# MPR121.net
KiCad netlist of a schematic drawn in Altium Designer
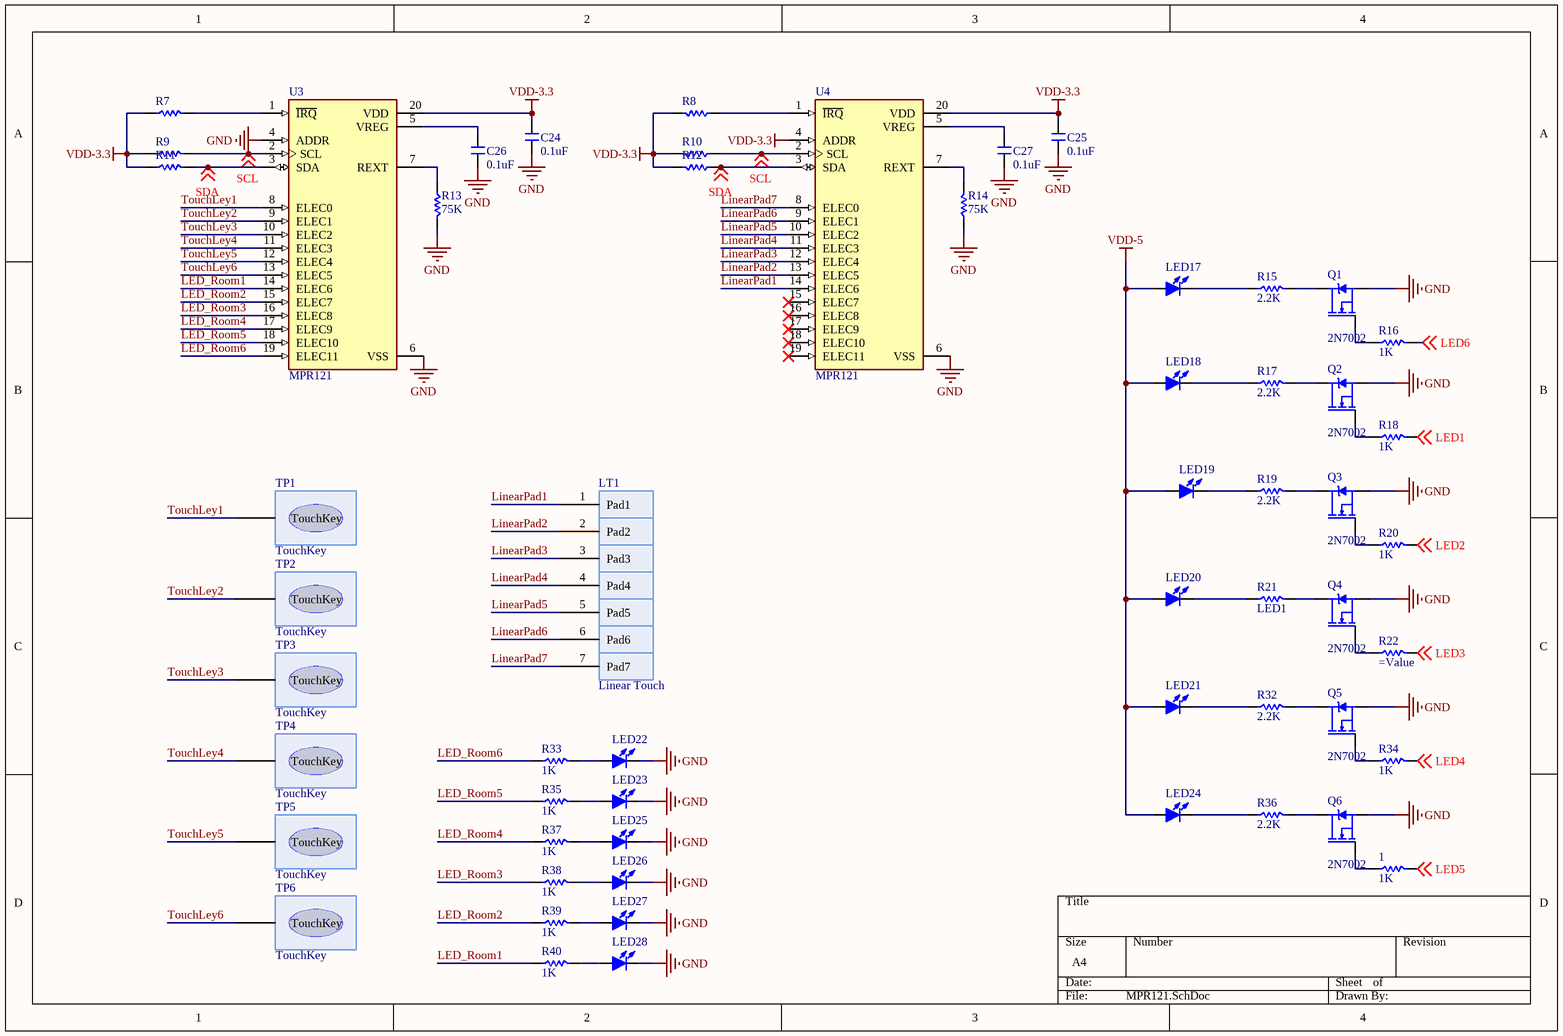
[diagram p0: MPR121.SchDoc]

(export (version "E")
  (design (tool "Eeschema 10.0.6"))
  (components
    (comp (ref "1")
      (value "1K")
      (footprint "R 0805")
      (description "Chip resistor")
      (fields (field (name "版权归属") "源创客"))
      (libsource (lib "Passive (Resistor-Capacitor-Inductor-Veristor-Ferrite)") (part "R"))
    )
    (comp (ref "C24")
      (value "0.1uF")
      (footprint "C 0603")
      (description "Non-polar patch capacitor")
      (fields (field (name "版权归属") "源创客"))
      (libsource (lib "Passive (Resistor-Capacitor-Inductor-Veristor-Ferrite)") (part "C"))
    )
    (comp (ref "C25")
      (value "0.1uF")
      (footprint "C 0603")
      (description "Non-polar patch capacitor")
      (fields (field (name "版权归属") "源创客"))
      (libsource (lib "Passive (Resistor-Capacitor-Inductor-Veristor-Ferrite)") (part "C"))
    )
    (comp (ref "C26")
      (value "0.1uF")
      (footprint "C 0603")
      (description "Non-polar patch capacitor")
      (fields (field (name "版权归属") "源创客"))
      (libsource (lib "Passive (Resistor-Capacitor-Inductor-Veristor-Ferrite)") (part "C"))
    )
    (comp (ref "C27")
      (value "0.1uF")
      (footprint "C 0603")
      (description "Non-polar patch capacitor")
      (fields (field (name "版权归属") "源创客"))
      (libsource (lib "Passive (Resistor-Capacitor-Inductor-Veristor-Ferrite)") (part "C"))
    )
    (comp (ref "LED17")
      (value "~")
      (footprint "LED 3MM-B")
      (description "Plug-in LED")
      (fields (field (name "版权归属") "源创客"))
      (libsource (lib "LED") (part "LED-3MM"))
    )
    (comp (ref "LED18")
      (value "~")
      (footprint "LED 3MM-B")
      (description "Plug-in LED")
      (fields (field (name "版权归属") "源创客"))
      (libsource (lib "LED") (part "LED-3MM"))
    )
    (comp (ref "LED19")
      (value "~")
      (footprint "LED 3MM-B")
      (description "Plug-in LED")
      (fields (field (name "版权归属") "源创客"))
      (libsource (lib "LED") (part "LED-3MM"))
    )
    (comp (ref "LED20")
      (value "~")
      (footprint "LED 3MM-B")
      (description "Plug-in LED")
      (fields (field (name "版权归属") "源创客"))
      (libsource (lib "LED") (part "LED-3MM"))
    )
    (comp (ref "LED21")
      (value "~")
      (footprint "LED 3MM-B")
      (description "Plug-in LED")
      (fields (field (name "版权归属") "源创客"))
      (libsource (lib "LED") (part "LED-3MM"))
    )
    (comp (ref "LED22")
      (value "LED-SMD")
      (footprint "LED 1206Y")
      (description "Patch LED")
      (fields (field (name "版权归属") "源创客"))
      (libsource (lib "LED") (part "LED-SMD"))
    )
    (comp (ref "LED23")
      (value "LED-SMD")
      (footprint "LED 1206Y")
      (description "Patch LED")
      (fields (field (name "版权归属") "源创客"))
      (libsource (lib "LED") (part "LED-SMD"))
    )
    (comp (ref "LED24")
      (value "~")
      (footprint "LED 3MM-B")
      (description "Plug-in LED")
      (fields (field (name "版权归属") "源创客"))
      (libsource (lib "LED") (part "LED-3MM"))
    )
    (comp (ref "LED25")
      (value "LED-SMD")
      (footprint "LED 1206Y")
      (description "Patch LED")
      (fields (field (name "版权归属") "源创客"))
      (libsource (lib "LED") (part "LED-SMD"))
    )
    (comp (ref "LED26")
      (value "LED-SMD")
      (footprint "LED 1206Y")
      (description "Patch LED")
      (fields (field (name "版权归属") "源创客"))
      (libsource (lib "LED") (part "LED-SMD"))
    )
    (comp (ref "LED27")
      (value "LED-SMD")
      (footprint "LED 1206Y")
      (description "Patch LED")
      (fields (field (name "版权归属") "源创客"))
      (libsource (lib "LED") (part "LED-SMD"))
    )
    (comp (ref "LED28")
      (value "LED-SMD")
      (footprint "LED 1206Y")
      (description "Patch LED")
      (fields (field (name "版权归属") "源创客"))
      (libsource (lib "LED") (part "LED-SMD"))
    )
    (comp (ref "LT1")
      (value "Linear Touch")
      (footprint "Linear TouchPad (7Pad)")
      (libsource (lib "Mechanical Components") (part "Linear Touch"))
    )
    (comp (ref "Q1")
      (value "2N7002")
      (footprint "SOT23-3")
      (description "N-Channel 60V 115mA (Tc) 225mW (Ta) Surface Mount SOT-23-3 (TO-236)")
      (fields (field (name "MF") "STMicroelectronics"))
      (libsource (lib "2N7002") (part "2N7002"))
    )
    (comp (ref "Q2")
      (value "2N7002")
      (footprint "SOT23-3")
      (description "N-Channel 60V 115mA (Tc) 225mW (Ta) Surface Mount SOT-23-3 (TO-236)")
      (fields (field (name "MF") "STMicroelectronics"))
      (libsource (lib "2N7002") (part "2N7002"))
    )
    (comp (ref "Q3")
      (value "2N7002")
      (footprint "SOT23-3")
      (description "N-Channel 60V 115mA (Tc) 225mW (Ta) Surface Mount SOT-23-3 (TO-236)")
      (fields (field (name "MF") "STMicroelectronics"))
      (libsource (lib "2N7002") (part "2N7002"))
    )
    (comp (ref "Q4")
      (value "2N7002")
      (footprint "SOT23-3")
      (description "N-Channel 60V 115mA (Tc) 225mW (Ta) Surface Mount SOT-23-3 (TO-236)")
      (fields (field (name "MF") "STMicroelectronics"))
      (libsource (lib "2N7002") (part "2N7002"))
    )
    (comp (ref "Q5")
      (value "2N7002")
      (footprint "SOT23-3")
      (description "N-Channel 60V 115mA (Tc) 225mW (Ta) Surface Mount SOT-23-3 (TO-236)")
      (fields (field (name "MF") "STMicroelectronics"))
      (libsource (lib "2N7002") (part "2N7002"))
    )
    (comp (ref "Q6")
      (value "2N7002")
      (footprint "SOT23-3")
      (description "N-Channel 60V 115mA (Tc) 225mW (Ta) Surface Mount SOT-23-3 (TO-236)")
      (fields (field (name "MF") "STMicroelectronics"))
      (libsource (lib "2N7002") (part "2N7002"))
    )
    (comp (ref "R7")
      (value "~")
      (footprint "R 0603")
      (description "Chip resistor")
      (fields (field (name "版权归属") "源创客"))
      (libsource (lib "Passive (Resistor-Capacitor-Inductor-Veristor-Ferrite)") (part "R"))
    )
    (comp (ref "R8")
      (value "~")
      (footprint "R 0603")
      (description "Chip resistor")
      (fields (field (name "版权归属") "源创客"))
      (libsource (lib "Passive (Resistor-Capacitor-Inductor-Veristor-Ferrite)") (part "R"))
    )
    (comp (ref "R9")
      (value "~")
      (footprint "R 0603")
      (description "Chip resistor")
      (fields (field (name "版权归属") "源创客"))
      (libsource (lib "Passive (Resistor-Capacitor-Inductor-Veristor-Ferrite)") (part "R"))
    )
    (comp (ref "R10")
      (value "~")
      (footprint "R 0603")
      (description "Chip resistor")
      (fields (field (name "版权归属") "源创客"))
      (libsource (lib "Passive (Resistor-Capacitor-Inductor-Veristor-Ferrite)") (part "R"))
    )
    (comp (ref "R11")
      (value "~")
      (footprint "R 0603")
      (description "Chip resistor")
      (fields (field (name "版权归属") "源创客"))
      (libsource (lib "Passive (Resistor-Capacitor-Inductor-Veristor-Ferrite)") (part "R"))
    )
    (comp (ref "R12")
      (value "~")
      (footprint "R 0603")
      (description "Chip resistor")
      (fields (field (name "版权归属") "源创客"))
      (libsource (lib "Passive (Resistor-Capacitor-Inductor-Veristor-Ferrite)") (part "R"))
    )
    (comp (ref "R13")
      (value "75K")
      (footprint "R 0603")
      (description "Chip resistor")
      (fields (field (name "版权归属") "源创客"))
      (libsource (lib "Passive (Resistor-Capacitor-Inductor-Veristor-Ferrite)") (part "R"))
    )
    (comp (ref "R14")
      (value "75K")
      (footprint "R 0603")
      (description "Chip resistor")
      (fields (field (name "版权归属") "源创客"))
      (libsource (lib "Passive (Resistor-Capacitor-Inductor-Veristor-Ferrite)") (part "R"))
    )
    (comp (ref "R15")
      (value "2.2K")
      (footprint "R 0805")
      (description "Chip resistor")
      (fields (field (name "版权归属") "源创客"))
      (libsource (lib "Passive (Resistor-Capacitor-Inductor-Veristor-Ferrite)") (part "R"))
    )
    (comp (ref "R16")
      (value "1K")
      (footprint "R 0805")
      (description "Chip resistor")
      (fields (field (name "版权归属") "源创客"))
      (libsource (lib "Passive (Resistor-Capacitor-Inductor-Veristor-Ferrite)") (part "R"))
    )
    (comp (ref "R17")
      (value "2.2K")
      (footprint "R 0805")
      (description "Chip resistor")
      (fields (field (name "版权归属") "源创客"))
      (libsource (lib "Passive (Resistor-Capacitor-Inductor-Veristor-Ferrite)") (part "R"))
    )
    (comp (ref "R18")
      (value "1K")
      (footprint "R 0805")
      (description "Chip resistor")
      (fields (field (name "版权归属") "源创客"))
      (libsource (lib "Passive (Resistor-Capacitor-Inductor-Veristor-Ferrite)") (part "R"))
    )
    (comp (ref "R19")
      (value "2.2K")
      (footprint "R 0805")
      (description "Chip resistor")
      (fields (field (name "版权归属") "源创客"))
      (libsource (lib "Passive (Resistor-Capacitor-Inductor-Veristor-Ferrite)") (part "R"))
    )
    (comp (ref "R20")
      (value "1K")
      (footprint "R 0805")
      (description "Chip resistor")
      (fields (field (name "版权归属") "源创客"))
      (libsource (lib "Passive (Resistor-Capacitor-Inductor-Veristor-Ferrite)") (part "R"))
    )
    (comp (ref "R21")
      (value "LED1")
      (footprint "R 0805")
      (description "Chip resistor")
      (fields (field (name "版权归属") "源创客"))
      (libsource (lib "Passive (Resistor-Capacitor-Inductor-Veristor-Ferrite)") (part "R"))
    )
    (comp (ref "R22")
      (value "~")
      (footprint "R 0805")
      (description "Chip resistor")
      (fields (field (name "版权归属") "源创客"))
      (libsource (lib "Passive (Resistor-Capacitor-Inductor-Veristor-Ferrite)") (part "R"))
    )
    (comp (ref "R32")
      (value "2.2K")
      (footprint "R 0805")
      (description "Chip resistor")
      (fields (field (name "版权归属") "源创客"))
      (libsource (lib "Passive (Resistor-Capacitor-Inductor-Veristor-Ferrite)") (part "R"))
    )
    (comp (ref "R33")
      (value "1K")
      (footprint "R 0805")
      (description "Chip resistor")
      (fields (field (name "版权归属") "源创客"))
      (libsource (lib "Passive (Resistor-Capacitor-Inductor-Veristor-Ferrite)") (part "R"))
    )
    (comp (ref "R34")
      (value "1K")
      (footprint "R 0805")
      (description "Chip resistor")
      (fields (field (name "版权归属") "源创客"))
      (libsource (lib "Passive (Resistor-Capacitor-Inductor-Veristor-Ferrite)") (part "R"))
    )
    (comp (ref "R35")
      (value "1K")
      (footprint "R 0805")
      (description "Chip resistor")
      (fields (field (name "版权归属") "源创客"))
      (libsource (lib "Passive (Resistor-Capacitor-Inductor-Veristor-Ferrite)") (part "R"))
    )
    (comp (ref "R36")
      (value "2.2K")
      (footprint "R 0805")
      (description "Chip resistor")
      (fields (field (name "版权归属") "源创客"))
      (libsource (lib "Passive (Resistor-Capacitor-Inductor-Veristor-Ferrite)") (part "R"))
    )
    (comp (ref "R37")
      (value "1K")
      (footprint "R 0805")
      (description "Chip resistor")
      (fields (field (name "版权归属") "源创客"))
      (libsource (lib "Passive (Resistor-Capacitor-Inductor-Veristor-Ferrite)") (part "R"))
    )
    (comp (ref "R38")
      (value "1K")
      (footprint "R 0805")
      (description "Chip resistor")
      (fields (field (name "版权归属") "源创客"))
      (libsource (lib "Passive (Resistor-Capacitor-Inductor-Veristor-Ferrite)") (part "R"))
    )
    (comp (ref "R39")
      (value "1K")
      (footprint "R 0805")
      (description "Chip resistor")
      (fields (field (name "版权归属") "源创客"))
      (libsource (lib "Passive (Resistor-Capacitor-Inductor-Veristor-Ferrite)") (part "R"))
    )
    (comp (ref "R40")
      (value "1K")
      (footprint "R 0805")
      (description "Chip resistor")
      (fields (field (name "版权归属") "源创客"))
      (libsource (lib "Passive (Resistor-Capacitor-Inductor-Veristor-Ferrite)") (part "R"))
    )
    (comp (ref "TP1")
      (value "TouchKey")
      (footprint "Square TouchKey (1.5cm)")
      (libsource (lib "Mechanical Components") (part "TouchKey"))
    )
    (comp (ref "TP2")
      (value "TouchKey")
      (footprint "Square TouchKey (1.5cm)")
      (libsource (lib "Mechanical Components") (part "TouchKey"))
    )
    (comp (ref "TP3")
      (value "TouchKey")
      (footprint "Square TouchKey (1.5cm)")
      (libsource (lib "Mechanical Components") (part "TouchKey"))
    )
    (comp (ref "TP4")
      (value "TouchKey")
      (footprint "Square TouchKey (1.5cm)")
      (libsource (lib "Mechanical Components") (part "TouchKey"))
    )
    (comp (ref "TP5")
      (value "TouchKey")
      (footprint "Square TouchKey (1.5cm)")
      (libsource (lib "Mechanical Components") (part "TouchKey"))
    )
    (comp (ref "TP6")
      (value "TouchKey")
      (footprint "Square TouchKey (1.5cm)")
      (libsource (lib "Mechanical Components") (part "TouchKey"))
    )
    (comp (ref "U3")
      (value "MPR121")
      (footprint "QFN-20Pin")
      (libsource (lib "Integrated Circuit") (part "MPR121"))
    )
    (comp (ref "U4")
      (value "MPR121")
      (footprint "QFN-20Pin")
      (libsource (lib "Integrated Circuit") (part "MPR121"))
    )
  )
  (nets
    (net (code "1") (name "/LED_Room1") (class "Default")
      (node (ref "R40") (pin "1") (pinfunction "1_1") (pintype "passive"))
      (node (ref "U3") (pin "14") (pinfunction "ELEC6_14") (pintype "input"))
    )
    (net (code "2") (name "/LED_Room2") (class "Default")
      (node (ref "R39") (pin "1") (pinfunction "1_1") (pintype "passive"))
      (node (ref "U3") (pin "15") (pinfunction "ELEC7_15") (pintype "input"))
    )
    (net (code "3") (name "/LED_Room3") (class "Default")
      (node (ref "R38") (pin "1") (pinfunction "1_1") (pintype "passive"))
      (node (ref "U3") (pin "16") (pinfunction "ELEC8_16") (pintype "input"))
    )
    (net (code "4") (name "/LED_Room4") (class "Default")
      (node (ref "R37") (pin "1") (pinfunction "1_1") (pintype "passive"))
      (node (ref "U3") (pin "17") (pinfunction "ELEC9_17") (pintype "input"))
    )
    (net (code "5") (name "/LED_Room5") (class "Default")
      (node (ref "R35") (pin "1") (pinfunction "1_1") (pintype "passive"))
      (node (ref "U3") (pin "18") (pinfunction "ELEC10_18") (pintype "input"))
    )
    (net (code "6") (name "/LED_Room6") (class "Default")
      (node (ref "R33") (pin "1") (pinfunction "1_1") (pintype "passive"))
      (node (ref "U3") (pin "19") (pinfunction "ELEC11_19") (pintype "input"))
    )
    (net (code "7") (name "/LinearPad1") (class "Default")
      (node (ref "LT1") (pin "1") (pinfunction "Pad1_1") (pintype "passive"))
      (node (ref "U4") (pin "14") (pinfunction "ELEC6_14") (pintype "input"))
    )
    (net (code "8") (name "/LinearPad2") (class "Default")
      (node (ref "LT1") (pin "2") (pinfunction "Pad2_2") (pintype "passive"))
      (node (ref "U4") (pin "13") (pinfunction "ELEC5_13") (pintype "input"))
    )
    (net (code "9") (name "/LinearPad3") (class "Default")
      (node (ref "LT1") (pin "3") (pinfunction "Pad3_3") (pintype "passive"))
      (node (ref "U4") (pin "12") (pinfunction "ELEC4_12") (pintype "input"))
    )
    (net (code "10") (name "/LinearPad4") (class "Default")
      (node (ref "LT1") (pin "4") (pinfunction "Pad4_4") (pintype "passive"))
      (node (ref "U4") (pin "11") (pinfunction "ELEC3_11") (pintype "input"))
    )
    (net (code "11") (name "/LinearPad5") (class "Default")
      (node (ref "LT1") (pin "5") (pinfunction "Pad5_5") (pintype "passive"))
      (node (ref "U4") (pin "10") (pinfunction "ELEC2_10") (pintype "input"))
    )
    (net (code "12") (name "/LinearPad6") (class "Default")
      (node (ref "LT1") (pin "6") (pinfunction "Pad6_6") (pintype "passive"))
      (node (ref "U4") (pin "9") (pinfunction "ELEC1_9") (pintype "input"))
    )
    (net (code "13") (name "/LinearPad7") (class "Default")
      (node (ref "LT1") (pin "7") (pinfunction "Pad7_7") (pintype "passive"))
      (node (ref "U4") (pin "8") (pinfunction "ELEC0_8") (pintype "input"))
    )
    (net (code "14") (name "/TouchLey1") (class "Default")
      (node (ref "TP1") (pin "1") (pinfunction "TouchKey_1") (pintype "passive"))
      (node (ref "U3") (pin "8") (pinfunction "ELEC0_8") (pintype "input"))
    )
    (net (code "15") (name "/TouchLey2") (class "Default")
      (node (ref "TP2") (pin "1") (pinfunction "TouchKey_1") (pintype "passive"))
      (node (ref "U3") (pin "9") (pinfunction "ELEC1_9") (pintype "input"))
    )
    (net (code "16") (name "/TouchLey3") (class "Default")
      (node (ref "TP3") (pin "1") (pinfunction "TouchKey_1") (pintype "passive"))
      (node (ref "U3") (pin "10") (pinfunction "ELEC2_10") (pintype "input"))
    )
    (net (code "17") (name "/TouchLey4") (class "Default")
      (node (ref "TP4") (pin "1") (pinfunction "TouchKey_1") (pintype "passive"))
      (node (ref "U3") (pin "11") (pinfunction "ELEC3_11") (pintype "input"))
    )
    (net (code "18") (name "/TouchLey5") (class "Default")
      (node (ref "TP5") (pin "1") (pinfunction "TouchKey_1") (pintype "passive"))
      (node (ref "U3") (pin "12") (pinfunction "ELEC4_12") (pintype "input"))
    )
    (net (code "19") (name "/TouchLey6") (class "Default")
      (node (ref "TP6") (pin "1") (pinfunction "TouchKey_1") (pintype "passive"))
      (node (ref "U3") (pin "13") (pinfunction "ELEC5_13") (pintype "input"))
    )
    (net (code "20") (name "GND") (class "Default")
      (node (ref "C24") (pin "1") (pinfunction "1_1") (pintype "passive"))
      (node (ref "C25") (pin "1") (pinfunction "1_1") (pintype "passive"))
      (node (ref "C26") (pin "1") (pinfunction "1_1") (pintype "passive"))
      (node (ref "C27") (pin "1") (pinfunction "1_1") (pintype "passive"))
      (node (ref "LED22") (pin "2") (pinfunction "K_2") (pintype "passive"))
      (node (ref "LED23") (pin "2") (pinfunction "K_2") (pintype "passive"))
      (node (ref "LED25") (pin "2") (pinfunction "K_2") (pintype "passive"))
      (node (ref "LED26") (pin "2") (pinfunction "K_2") (pintype "passive"))
      (node (ref "LED27") (pin "2") (pinfunction "K_2") (pintype "passive"))
      (node (ref "LED28") (pin "2") (pinfunction "K_2") (pintype "passive"))
      (node (ref "Q1") (pin "2") (pinfunction "S_2") (pintype "bidirectional"))
      (node (ref "Q2") (pin "2") (pinfunction "S_2") (pintype "bidirectional"))
      (node (ref "Q3") (pin "2") (pinfunction "S_2") (pintype "bidirectional"))
      (node (ref "Q4") (pin "2") (pinfunction "S_2") (pintype "bidirectional"))
      (node (ref "Q5") (pin "2") (pinfunction "S_2") (pintype "bidirectional"))
      (node (ref "Q6") (pin "2") (pinfunction "S_2") (pintype "bidirectional"))
      (node (ref "R13") (pin "2") (pinfunction "2_2") (pintype "passive"))
      (node (ref "R14") (pin "1") (pinfunction "1_1") (pintype "passive"))
      (node (ref "U3") (pin "4") (pinfunction "ADDR_4") (pintype "input"))
      (node (ref "U3") (pin "6") (pinfunction "VSS_6") (pintype "power_in"))
      (node (ref "U4") (pin "6") (pinfunction "VSS_6") (pintype "power_in"))
    )
    (net (code "21") (name "LED1") (class "Default")
      (node (ref "R18") (pin "2") (pinfunction "2_2") (pintype "passive"))
    )
    (net (code "22") (name "LED2") (class "Default")
      (node (ref "R20") (pin "2") (pinfunction "2_2") (pintype "passive"))
    )
    (net (code "23") (name "LED3") (class "Default")
      (node (ref "R22") (pin "2") (pinfunction "2_2") (pintype "passive"))
    )
    (net (code "24") (name "LED4") (class "Default")
      (node (ref "R34") (pin "2") (pinfunction "2_2") (pintype "passive"))
    )
    (net (code "25") (name "LED5") (class "Default")
      (node (ref "1") (pin "2") (pinfunction "2_2") (pintype "passive"))
    )
    (net (code "26") (name "LED6") (class "Default")
      (node (ref "R16") (pin "2") (pinfunction "2_2") (pintype "passive"))
    )
    (net (code "27") (name "Net-(LED17-K)") (class "Default")
      (node (ref "LED17") (pin "2") (pinfunction "K_2") (pintype "passive"))
      (node (ref "R15") (pin "1") (pinfunction "1_1") (pintype "passive"))
    )
    (net (code "28") (name "Net-(LED18-K)") (class "Default")
      (node (ref "LED18") (pin "2") (pinfunction "K_2") (pintype "passive"))
      (node (ref "R17") (pin "1") (pinfunction "1_1") (pintype "passive"))
    )
    (net (code "29") (name "Net-(LED19-K)") (class "Default")
      (node (ref "LED19") (pin "2") (pinfunction "K_2") (pintype "passive"))
      (node (ref "R19") (pin "1") (pinfunction "1_1") (pintype "passive"))
    )
    (net (code "30") (name "Net-(LED20-K)") (class "Default")
      (node (ref "LED20") (pin "2") (pinfunction "K_2") (pintype "passive"))
      (node (ref "R21") (pin "1") (pinfunction "1_1") (pintype "passive"))
    )
    (net (code "31") (name "Net-(LED21-K)") (class "Default")
      (node (ref "LED21") (pin "2") (pinfunction "K_2") (pintype "passive"))
      (node (ref "R32") (pin "1") (pinfunction "1_1") (pintype "passive"))
    )
    (net (code "32") (name "Net-(LED22-A)") (class "Default")
      (node (ref "LED22") (pin "1") (pinfunction "A_1") (pintype "passive"))
      (node (ref "R33") (pin "2") (pinfunction "2_2") (pintype "passive"))
    )
    (net (code "33") (name "Net-(LED23-A)") (class "Default")
      (node (ref "LED23") (pin "1") (pinfunction "A_1") (pintype "passive"))
      (node (ref "R35") (pin "2") (pinfunction "2_2") (pintype "passive"))
    )
    (net (code "34") (name "Net-(LED24-K)") (class "Default")
      (node (ref "LED24") (pin "2") (pinfunction "K_2") (pintype "passive"))
      (node (ref "R36") (pin "1") (pinfunction "1_1") (pintype "passive"))
    )
    (net (code "35") (name "Net-(LED25-A)") (class "Default")
      (node (ref "LED25") (pin "1") (pinfunction "A_1") (pintype "passive"))
      (node (ref "R37") (pin "2") (pinfunction "2_2") (pintype "passive"))
    )
    (net (code "36") (name "Net-(LED26-A)") (class "Default")
      (node (ref "LED26") (pin "1") (pinfunction "A_1") (pintype "passive"))
      (node (ref "R38") (pin "2") (pinfunction "2_2") (pintype "passive"))
    )
    (net (code "37") (name "Net-(LED27-A)") (class "Default")
      (node (ref "LED27") (pin "1") (pinfunction "A_1") (pintype "passive"))
      (node (ref "R39") (pin "2") (pinfunction "2_2") (pintype "passive"))
    )
    (net (code "38") (name "Net-(LED28-A)") (class "Default")
      (node (ref "LED28") (pin "1") (pinfunction "A_1") (pintype "passive"))
      (node (ref "R40") (pin "2") (pinfunction "2_2") (pintype "passive"))
    )
    (net (code "39") (name "Net-(Q1-D)") (class "Default")
      (node (ref "Q1") (pin "3") (pinfunction "D_3") (pintype "bidirectional"))
      (node (ref "R15") (pin "2") (pinfunction "2_2") (pintype "passive"))
    )
    (net (code "40") (name "Net-(Q1-G)") (class "Default")
      (node (ref "Q1") (pin "1") (pinfunction "G_1") (pintype "bidirectional"))
      (node (ref "R16") (pin "1") (pinfunction "1_1") (pintype "passive"))
    )
    (net (code "41") (name "Net-(Q2-D)") (class "Default")
      (node (ref "Q2") (pin "3") (pinfunction "D_3") (pintype "bidirectional"))
      (node (ref "R17") (pin "2") (pinfunction "2_2") (pintype "passive"))
    )
    (net (code "42") (name "Net-(Q2-G)") (class "Default")
      (node (ref "Q2") (pin "1") (pinfunction "G_1") (pintype "bidirectional"))
      (node (ref "R18") (pin "1") (pinfunction "1_1") (pintype "passive"))
    )
    (net (code "43") (name "Net-(Q3-D)") (class "Default")
      (node (ref "Q3") (pin "3") (pinfunction "D_3") (pintype "bidirectional"))
      (node (ref "R19") (pin "2") (pinfunction "2_2") (pintype "passive"))
    )
    (net (code "44") (name "Net-(Q3-G)") (class "Default")
      (node (ref "Q3") (pin "1") (pinfunction "G_1") (pintype "bidirectional"))
      (node (ref "R20") (pin "1") (pinfunction "1_1") (pintype "passive"))
    )
    (net (code "45") (name "Net-(Q4-D)") (class "Default")
      (node (ref "Q4") (pin "3") (pinfunction "D_3") (pintype "bidirectional"))
      (node (ref "R21") (pin "2") (pinfunction "2_2") (pintype "passive"))
    )
    (net (code "46") (name "Net-(Q4-G)") (class "Default")
      (node (ref "Q4") (pin "1") (pinfunction "G_1") (pintype "bidirectional"))
      (node (ref "R22") (pin "1") (pinfunction "1_1") (pintype "passive"))
    )
    (net (code "47") (name "Net-(Q5-D)") (class "Default")
      (node (ref "Q5") (pin "3") (pinfunction "D_3") (pintype "bidirectional"))
      (node (ref "R32") (pin "2") (pinfunction "2_2") (pintype "passive"))
    )
    (net (code "48") (name "Net-(Q5-G)") (class "Default")
      (node (ref "Q5") (pin "1") (pinfunction "G_1") (pintype "bidirectional"))
      (node (ref "R34") (pin "1") (pinfunction "1_1") (pintype "passive"))
    )
    (net (code "49") (name "Net-(Q6-D)") (class "Default")
      (node (ref "Q6") (pin "3") (pinfunction "D_3") (pintype "bidirectional"))
      (node (ref "R36") (pin "2") (pinfunction "2_2") (pintype "passive"))
    )
    (net (code "50") (name "Net-(Q6-G)") (class "Default")
      (node (ref "1") (pin "1") (pinfunction "1_1") (pintype "passive"))
      (node (ref "Q6") (pin "1") (pinfunction "G_1") (pintype "bidirectional"))
    )
    (net (code "51") (name "Net-(U3-REXT)") (class "Default")
      (node (ref "R13") (pin "1") (pinfunction "1_1") (pintype "passive"))
      (node (ref "U3") (pin "7") (pinfunction "REXT_7") (pintype "passive"))
    )
    (net (code "52") (name "Net-(U3-VREG)") (class "Default")
      (node (ref "C26") (pin "2") (pinfunction "2_2") (pintype "passive"))
      (node (ref "U3") (pin "5") (pinfunction "VREG_5") (pintype "power_in"))
    )
    (net (code "53") (name "Net-(U3-~{IRQ})") (class "Default")
      (node (ref "R7") (pin "2") (pinfunction "2_2") (pintype "passive"))
      (node (ref "U3") (pin "1") (pinfunction "~{IRQ}_1") (pintype "input"))
    )
    (net (code "54") (name "Net-(U4-REXT)") (class "Default")
      (node (ref "R14") (pin "2") (pinfunction "2_2") (pintype "passive"))
      (node (ref "U4") (pin "7") (pinfunction "REXT_7") (pintype "passive"))
    )
    (net (code "55") (name "Net-(U4-VREG)") (class "Default")
      (node (ref "C27") (pin "2") (pinfunction "2_2") (pintype "passive"))
      (node (ref "U4") (pin "5") (pinfunction "VREG_5") (pintype "power_in"))
    )
    (net (code "56") (name "Net-(U4-~{IRQ})") (class "Default")
      (node (ref "R8") (pin "1") (pinfunction "1_1") (pintype "passive"))
      (node (ref "U4") (pin "1") (pinfunction "~{IRQ}_1") (pintype "input"))
    )
    (net (code "57") (name "SCL") (class "Default")
      (node (ref "R10") (pin "1") (pinfunction "1_1") (pintype "passive"))
      (node (ref "R9") (pin "2") (pinfunction "2_2") (pintype "passive"))
      (node (ref "U3") (pin "2") (pinfunction "SCL_2") (pintype "input"))
      (node (ref "U4") (pin "2") (pinfunction "SCL_2") (pintype "input"))
    )
    (net (code "58") (name "SDA") (class "Default")
      (node (ref "R11") (pin "2") (pinfunction "2_2") (pintype "passive"))
      (node (ref "R12") (pin "1") (pinfunction "1_1") (pintype "passive"))
      (node (ref "U3") (pin "3") (pinfunction "SDA_3") (pintype "bidirectional"))
      (node (ref "U4") (pin "3") (pinfunction "SDA_3") (pintype "bidirectional"))
    )
    (net (code "59") (name "VDD-3.3") (class "Default")
      (node (ref "C24") (pin "2") (pinfunction "2_2") (pintype "passive"))
      (node (ref "C25") (pin "2") (pinfunction "2_2") (pintype "passive"))
      (node (ref "R10") (pin "2") (pinfunction "2_2") (pintype "passive"))
      (node (ref "R11") (pin "1") (pinfunction "1_1") (pintype "passive"))
      (node (ref "R12") (pin "2") (pinfunction "2_2") (pintype "passive"))
      (node (ref "R7") (pin "1") (pinfunction "1_1") (pintype "passive"))
      (node (ref "R8") (pin "2") (pinfunction "2_2") (pintype "passive"))
      (node (ref "R9") (pin "1") (pinfunction "1_1") (pintype "passive"))
      (node (ref "U3") (pin "20") (pinfunction "VDD_20") (pintype "power_in"))
      (node (ref "U4") (pin "20") (pinfunction "VDD_20") (pintype "power_in"))
      (node (ref "U4") (pin "4") (pinfunction "ADDR_4") (pintype "input"))
    )
    (net (code "60") (name "VDD-5") (class "Default")
      (node (ref "LED17") (pin "1") (pinfunction "A_1") (pintype "passive"))
      (node (ref "LED18") (pin "1") (pinfunction "A_1") (pintype "passive"))
      (node (ref "LED19") (pin "1") (pinfunction "A_1") (pintype "passive"))
      (node (ref "LED20") (pin "1") (pinfunction "A_1") (pintype "passive"))
      (node (ref "LED21") (pin "1") (pinfunction "A_1") (pintype "passive"))
      (node (ref "LED24") (pin "1") (pinfunction "A_1") (pintype "passive"))
    )
    (net (code "61") (name "unconnected-(U4-ELEC7-Pad15)") (class "Default")
      (node (ref "U4") (pin "15") (pinfunction "ELEC7_15") (pintype "input+no_connect"))
    )
    (net (code "62") (name "unconnected-(U4-ELEC8-Pad16)") (class "Default")
      (node (ref "U4") (pin "16") (pinfunction "ELEC8_16") (pintype "input+no_connect"))
    )
    (net (code "63") (name "unconnected-(U4-ELEC9-Pad17)") (class "Default")
      (node (ref "U4") (pin "17") (pinfunction "ELEC9_17") (pintype "input+no_connect"))
    )
    (net (code "64") (name "unconnected-(U4-ELEC10-Pad18)") (class "Default")
      (node (ref "U4") (pin "18") (pinfunction "ELEC10_18") (pintype "input+no_connect"))
    )
    (net (code "65") (name "unconnected-(U4-ELEC11-Pad19)") (class "Default")
      (node (ref "U4") (pin "19") (pinfunction "ELEC11_19") (pintype "input+no_connect"))
    )
  )
)
